# MemoryLatch.net
KiCad netlist of a schematic drawn in Altium Designer
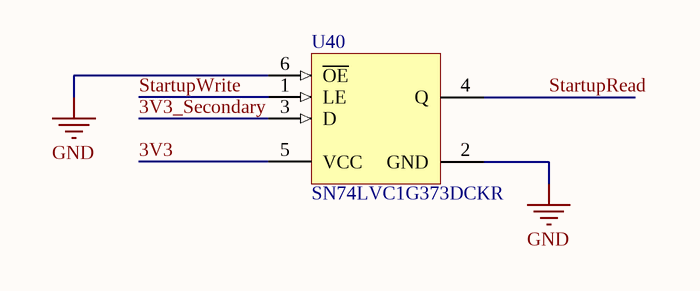
[diagram p0: MemoryLatch.SchDoc]

(export (version "E")
  (design (tool "Eeschema 10.0.6"))
  (components
    (comp (ref "U40")
      (value "SN74LVC1G373DCKR")
      (footprint "DCK0006A_M")
      (description "Bus Driver, LVC/LCX/Z Series, 1-Func, 1-Bit, True Output, CMOS, PDSO6")
      (libsource (lib "UGA SSRL Hardware Team") (part "TI-SN74LVC1G373-6"))
    )
  )
  (nets
    (net (code "1") (name "/3V3") (class "Default")
      (node (ref "U40") (pin "5") (pinfunction "VCC_5") (pintype "power_in"))
    )
    (net (code "2") (name "/3V3_Secondary") (class "Default")
      (node (ref "U40") (pin "3") (pinfunction "D_3") (pintype "input"))
    )
    (net (code "3") (name "/StartupRead") (class "Default")
      (node (ref "U40") (pin "4") (pinfunction "Q_4") (pintype "tri_state"))
    )
    (net (code "4") (name "/StartupWrite") (class "Default")
      (node (ref "U40") (pin "1") (pinfunction "LE_1") (pintype "input"))
    )
    (net (code "5") (name "GND") (class "Default")
      (node (ref "U40") (pin "2") (pinfunction "GND_2") (pintype "power_in"))
      (node (ref "U40") (pin "6") (pinfunction "~{OE}_6") (pintype "input"))
    )
  )
)
